# Hub_02.net
KiCad netlist of a schematic drawn in EAGLE
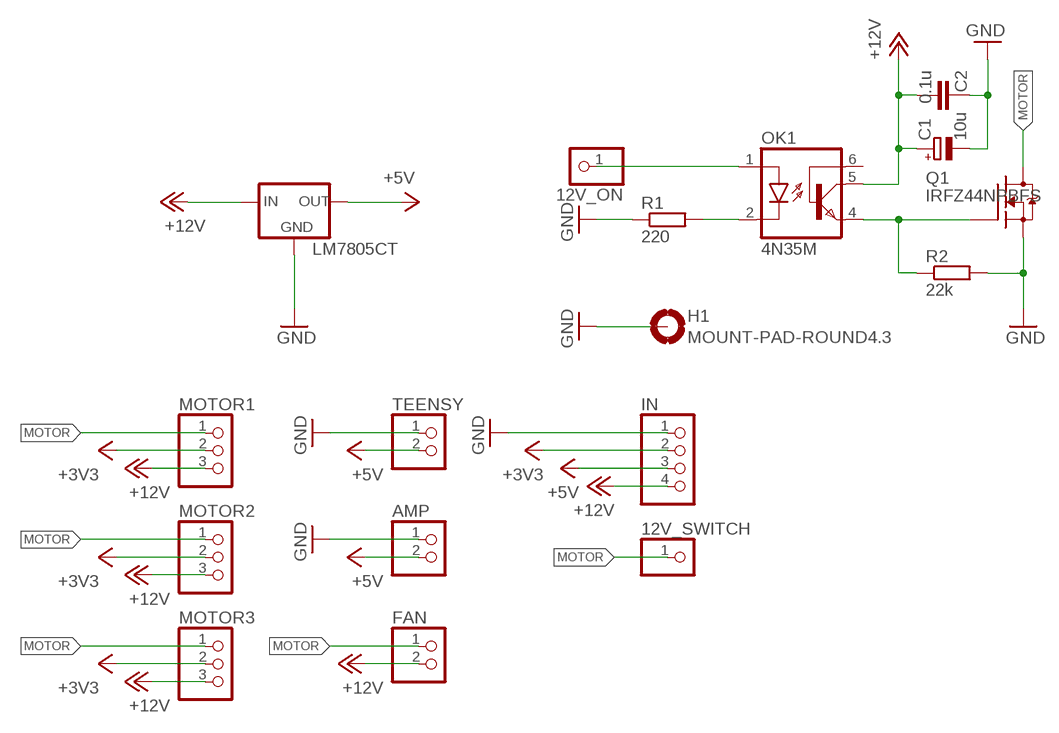
[diagram p0: schematic, sheet 1]

(export (version "E")
  (design (tool "Eeschema 10.0.6"))
  (components
    (comp (ref "12V_ON")
      (value "PINHD-1X1")
      (footprint "eagle-import:1X01")
      (libsource (lib "eagle-import") (part "PINHD-1X1"))
    )
    (comp (ref "12V_SWITCH")
      (value "PINHD-1X1")
      (footprint "eagle-import:1X01")
      (libsource (lib "eagle-import") (part "PINHD-1X1"))
    )
    (comp (ref "AMP")
      (value "PINHD-1X2")
      (footprint "eagle-import:1X02")
      (libsource (lib "eagle-import") (part "PINHD-1X2"))
    )
    (comp (ref "C1")
      (value "10u")
      (footprint "eagle-import:E2,5-6E")
      (libsource (lib "eagle-import") (part "CPOL-EUE2,5-6E"))
    )
    (comp (ref "C2")
      (value "0.1u")
      (footprint "eagle-import:C025-024X044")
      (libsource (lib "eagle-import") (part "C-EU025-024X044"))
    )
    (comp (ref "FAN")
      (value "PINHD-1X2")
      (footprint "eagle-import:1X02")
      (libsource (lib "eagle-import") (part "PINHD-1X2"))
    )
    (comp (ref "H1")
      (value "MOUNT-PAD-ROUND4.3")
      (footprint "eagle-import:4,3-PAD")
      (libsource (lib "eagle-import") (part "MOUNT-PAD-ROUND4.3"))
    )
    (comp (ref "IN")
      (value "PINHD-1X4")
      (footprint "eagle-import:1X04")
      (libsource (lib "eagle-import") (part "PINHD-1X4"))
    )
    (comp (ref "LM7805CT")
      (value "78XXS")
      (footprint "eagle-import:78XXS")
      (libsource (lib "eagle-import") (part "78XXS"))
    )
    (comp (ref "MOTOR1")
      (value "PINHD-1X3")
      (footprint "eagle-import:1X03")
      (libsource (lib "eagle-import") (part "PINHD-1X3"))
    )
    (comp (ref "MOTOR2")
      (value "PINHD-1X3")
      (footprint "eagle-import:1X03")
      (libsource (lib "eagle-import") (part "PINHD-1X3"))
    )
    (comp (ref "MOTOR3")
      (value "PINHD-1X3")
      (footprint "eagle-import:1X03")
      (libsource (lib "eagle-import") (part "PINHD-1X3"))
    )
    (comp (ref "OK1")
      (value "4N35M")
      (footprint "eagle-import:DIL06")
      (fields (field (name "MPN") "4N35-M"))
      (libsource (lib "eagle-import") (part "4N?M35"))
    )
    (comp (ref "Q1")
      (value "IRFZ44NPBFS")
      (footprint "eagle-import:TO220-3S")
      (libsource (lib "eagle-import") (part "IRFZ44NPBFS"))
    )
    (comp (ref "R1")
      (value "220")
      (footprint "eagle-import:0204_7")
      (libsource (lib "eagle-import") (part "R-EU_0204/7"))
    )
    (comp (ref "R2")
      (value "22k")
      (footprint "eagle-import:0204_7")
      (libsource (lib "eagle-import") (part "R-EU_0204/7"))
    )
    (comp (ref "TEENSY")
      (value "PINHD-1X2")
      (footprint "eagle-import:1X02")
      (libsource (lib "eagle-import") (part "PINHD-1X2"))
    )
  )
  (nets
    (net (code "1") (name "+3V3") (class "Default")
      (node (ref "IN") (pin "2") (pinfunction "2_2") (pintype "passive"))
      (node (ref "MOTOR1") (pin "2") (pinfunction "2_2") (pintype "passive"))
      (node (ref "MOTOR2") (pin "2") (pinfunction "2_2") (pintype "passive"))
      (node (ref "MOTOR3") (pin "2") (pinfunction "2_2") (pintype "passive"))
    )
    (net (code "2") (name "+5V") (class "Default")
      (node (ref "AMP") (pin "2") (pinfunction "2_2") (pintype "passive"))
      (node (ref "IN") (pin "3") (pinfunction "3_3") (pintype "passive"))
      (node (ref "LM7805CT") (pin "OUT") (pinfunction "OUT_OUT") (pintype "passive"))
      (node (ref "TEENSY") (pin "2") (pinfunction "2_2") (pintype "passive"))
    )
    (net (code "3") (name "+12V") (class "Default")
      (node (ref "C1") (pin "+") (pinfunction "+_+") (pintype "passive"))
      (node (ref "C2") (pin "2") (pinfunction "2_2") (pintype "passive"))
      (node (ref "FAN") (pin "2") (pinfunction "2_2") (pintype "passive"))
      (node (ref "IN") (pin "4") (pinfunction "4_4") (pintype "passive"))
      (node (ref "LM7805CT") (pin "IN") (pinfunction "IN_IN") (pintype "input"))
      (node (ref "MOTOR1") (pin "3") (pinfunction "3_3") (pintype "passive"))
      (node (ref "MOTOR2") (pin "3") (pinfunction "3_3") (pintype "passive"))
      (node (ref "MOTOR3") (pin "3") (pinfunction "3_3") (pintype "passive"))
      (node (ref "OK1") (pin "5") (pinfunction "COL_5") (pintype "passive"))
    )
    (net (code "4") (name "GND") (class "Default")
      (node (ref "AMP") (pin "1") (pinfunction "1_1") (pintype "passive"))
      (node (ref "C1") (pin "-") (pinfunction "-_-") (pintype "passive"))
      (node (ref "C2") (pin "1") (pinfunction "1_1") (pintype "passive"))
      (node (ref "H1") (pin "B4,3") (pinfunction "MOUNT_B4,3") (pintype "passive"))
      (node (ref "IN") (pin "1") (pinfunction "1_1") (pintype "passive"))
      (node (ref "LM7805CT") (pin "GND") (pinfunction "GND_GND") (pintype "input"))
      (node (ref "Q1") (pin "S") (pinfunction "S_S") (pintype "passive"))
      (node (ref "R1") (pin "1") (pinfunction "1_1") (pintype "passive"))
      (node (ref "R2") (pin "2") (pinfunction "2_2") (pintype "passive"))
      (node (ref "TEENSY") (pin "1") (pinfunction "1_1") (pintype "passive"))
    )
    (net (code "5") (name "MOTOR") (class "Default")
      (node (ref "12V_SWITCH") (pin "1") (pinfunction "1_1") (pintype "passive"))
      (node (ref "FAN") (pin "1") (pinfunction "1_1") (pintype "passive"))
      (node (ref "MOTOR1") (pin "1") (pinfunction "1_1") (pintype "passive"))
      (node (ref "MOTOR2") (pin "1") (pinfunction "1_1") (pintype "passive"))
      (node (ref "MOTOR3") (pin "1") (pinfunction "1_1") (pintype "passive"))
      (node (ref "Q1") (pin "D") (pinfunction "D_D") (pintype "passive"))
    )
    (net (code "6") (name "Net-(OK1-A)") (class "Default")
      (node (ref "12V_ON") (pin "1") (pinfunction "1_1") (pintype "passive"))
      (node (ref "OK1") (pin "1") (pinfunction "A_1") (pintype "passive"))
    )
    (net (code "7") (name "Net-(OK1-C)") (class "Default")
      (node (ref "OK1") (pin "2") (pinfunction "C_2") (pintype "passive"))
      (node (ref "R1") (pin "2") (pinfunction "2_2") (pintype "passive"))
    )
    (net (code "8") (name "Net-(OK1-EMI)") (class "Default")
      (node (ref "OK1") (pin "4") (pinfunction "EMI_4") (pintype "passive"))
      (node (ref "Q1") (pin "G") (pinfunction "G_G") (pintype "passive"))
      (node (ref "R2") (pin "1") (pinfunction "1_1") (pintype "passive"))
    )
    (net (code "9") (name "unconnected-(OK1-BAS-Pad6)") (class "Default")
      (node (ref "OK1") (pin "6") (pinfunction "BAS_6") (pintype "passive"))
    )
  )
)
